# ISL6236A_Sch.net
KiCad netlist of a schematic drawn in Altium Designer
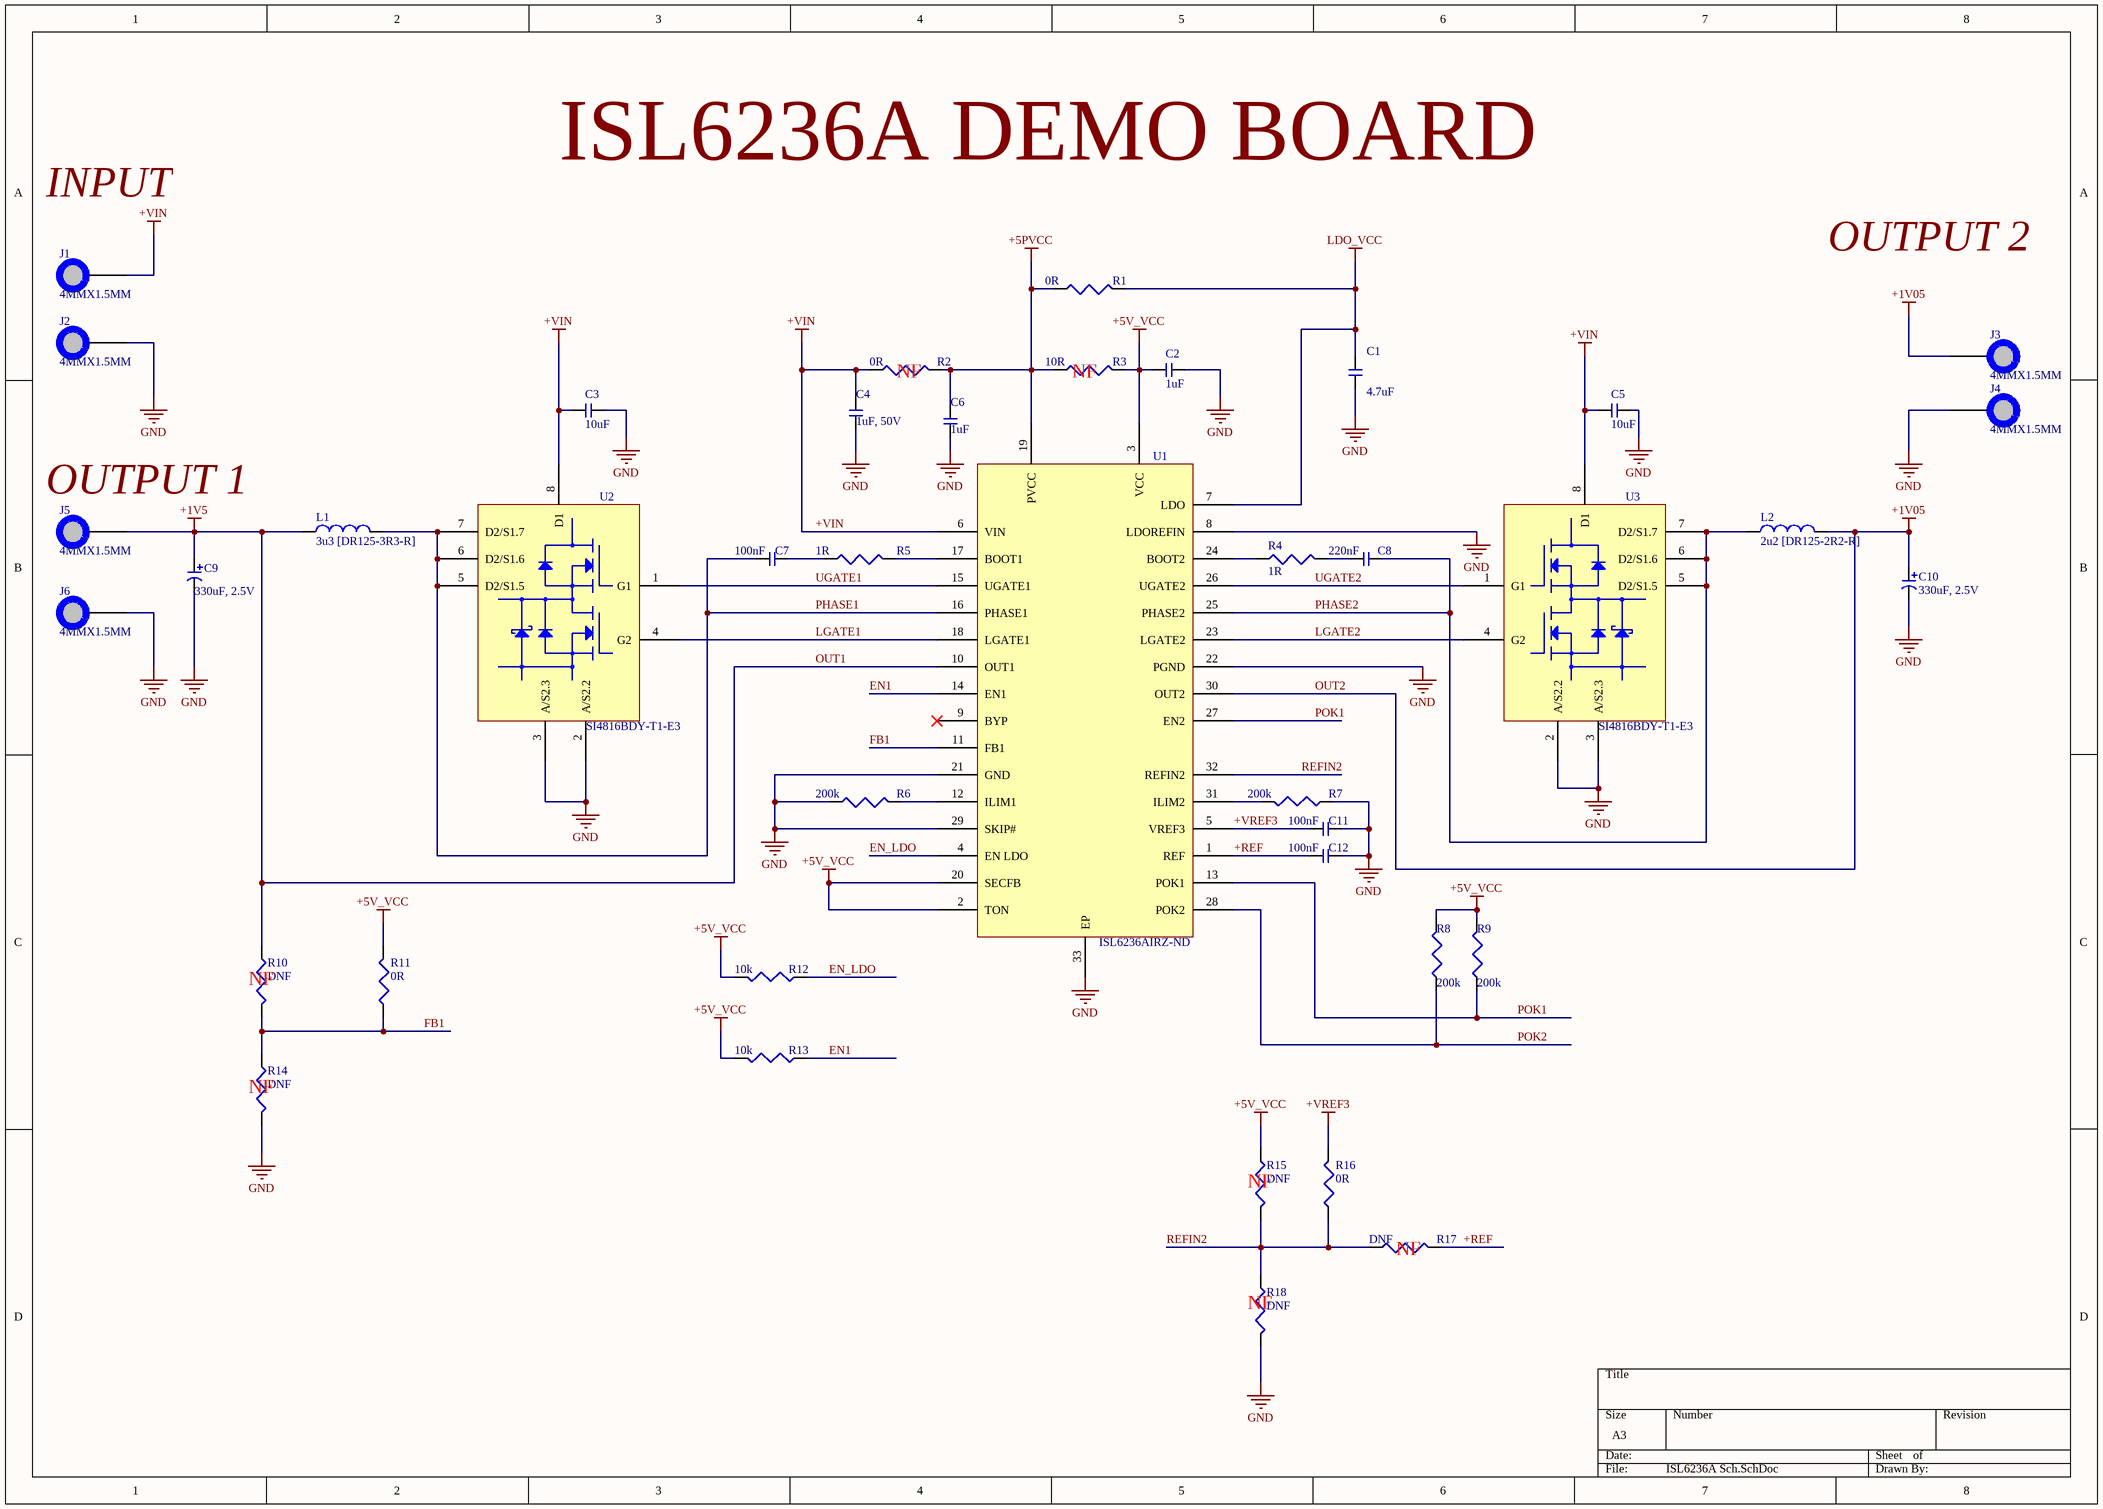
[diagram p0: ISL6236A Sch.SchDoc]

(export (version "E")
  (design (tool "Eeschema 10.0.6"))
  (components
    (comp (ref "C1")
      (value "4.7uF")
      (footprint "C0805")
      (description "CAP CER 4.7UF 10V Y5V 0805")
      (fields
        (field (name "MANUFACTURER") "Yageo")
        (field (name "MANUFACTURER PART NUMBER") "CC0805ZRY5V6BB475")
      )
      (libsource (lib "ISL6236A SchLib") (part "CC0805ZRY5V6BB475"))
    )
    (comp (ref "C2")
      (value "1uF")
      (footprint "C0805")
      (description "CAP CER 1UF 25V X5R 0805")
      (fields
        (field (name "MANUFACTURER") "AVX Corporation")
        (field (name "MANUFACTURER PART NUMBER") "08053D105KAT2A")
      )
      (libsource (lib "ISL6236A SchLib") (part "08053D105KAT2A"))
    )
    (comp (ref "C3")
      (value "10uF")
      (footprint "C1210")
      (description "CAP CER 10UF 25V X5R 1210")
      (fields
        (field (name "MANUFACTURER") "Wurth Electronics Inc")
        (field (name "MANUFACTURER PART NUMBER") "885012109013")
      )
      (libsource (lib "ISL6236A SchLib") (part "885012109013"))
    )
    (comp (ref "C4")
      (value "1uF, 50V")
      (footprint "C0805")
      (description "CAP CER 10000PF 50V NP0 0805")
      (fields
        (field (name "MANUFACTURER") "Murata Electronics North America")
        (field (name "MANUFACTURER PART NUMBER") "GRM2195C1H103FA01D")
      )
      (libsource (lib "ISL6236A SchLib") (part "GRM2195C1H103FA01D"))
    )
    (comp (ref "C5")
      (value "10uF")
      (footprint "C1210")
      (description "CAP CER 10UF 25V X5R 1210")
      (fields
        (field (name "MANUFACTURER") "Wurth Electronics Inc")
        (field (name "MANUFACTURER PART NUMBER") "885012109013")
      )
      (libsource (lib "ISL6236A SchLib") (part "885012109013"))
    )
    (comp (ref "C6")
      (value "1uF")
      (footprint "C0805")
      (description "CAP CER 1UF 25V X5R 0805")
      (fields
        (field (name "MANUFACTURER") "AVX Corporation")
        (field (name "MANUFACTURER PART NUMBER") "08053D105KAT2A")
      )
      (libsource (lib "ISL6236A SchLib") (part "08053D105KAT2A"))
    )
    (comp (ref "C7")
      (value "100nF")
      (footprint "C0805")
      (description "CAP CER 0.1UF 50V X7R 0805")
      (fields
        (field (name "MANUFACTURER") "AVX Corporation")
        (field (name "MANUFACTURER PART NUMBER") "08055C104KAT2A")
      )
      (libsource (lib "ISL6236A SchLib") (part "08055C104KAT2A"))
    )
    (comp (ref "C8")
      (value "220nF")
      (footprint "C1206")
      (description "CAP CER 0.22UF 50V Y5V 1206")
      (fields
        (field (name "MANUFACTURER") "Samsung Electro-Mechanics America, Inc.")
        (field (name "MANUFACTURER PART NUMBER") "CL31F224ZBCNNNC")
      )
      (libsource (lib "ISL6236A SchLib") (part "CL31F224ZBCNNNC"))
    )
    (comp (ref "C9")
      (value "330uF, 2.5V")
      (footprint "CPOL1210TCJ")
      (description "CAP TANT POLY 330UF 2.5V 1210")
      (fields
        (field (name "MANUFACTURER") "AVX Corporation")
        (field (name "MANUFACTURER PART NUMBER") "TCJB337M002R0070")
      )
      (libsource (lib "ISL6236A SchLib") (part "TCJB337M002R0070"))
    )
    (comp (ref "C10")
      (value "330uF, 2.5V")
      (footprint "CPOL1210TCJ")
      (description "CAP TANT POLY 330UF 2.5V 1210")
      (fields
        (field (name "MANUFACTURER") "AVX Corporation")
        (field (name "MANUFACTURER PART NUMBER") "TCJB337M002R0070")
      )
      (libsource (lib "ISL6236A SchLib") (part "TCJB337M002R0070"))
    )
    (comp (ref "C11")
      (value "100nF")
      (footprint "C0805")
      (description "CAP CER 0.1UF 50V X7R 0805")
      (fields
        (field (name "MANUFACTURER") "AVX Corporation")
        (field (name "MANUFACTURER PART NUMBER") "08055C104KAT2A")
      )
      (libsource (lib "ISL6236A SchLib") (part "08055C104KAT2A"))
    )
    (comp (ref "C12")
      (value "100nF")
      (footprint "C0805")
      (description "CAP CER 0.1UF 50V X7R 0805")
      (fields
        (field (name "MANUFACTURER") "AVX Corporation")
        (field (name "MANUFACTURER PART NUMBER") "08055C104KAT2A")
      )
      (libsource (lib "ISL6236A SchLib") (part "08055C104KAT2A"))
    )
    (comp (ref "J1")
      (value "4MMX1.5MM")
      (footprint "PAD_WITH_HOLE_4MMX1.5MM")
      (libsource (lib "ISL6236A SchLib") (part "PAD_WITH_HOLE_4MMX1.5MM"))
    )
    (comp (ref "J2")
      (value "4MMX1.5MM")
      (footprint "PAD_WITH_HOLE_4MMX1.5MM")
      (libsource (lib "ISL6236A SchLib") (part "PAD_WITH_HOLE_4MMX1.5MM"))
    )
    (comp (ref "J3")
      (value "4MMX1.5MM")
      (footprint "PAD_WITH_HOLE_4MMX1.5MM")
      (libsource (lib "ISL6236A SchLib") (part "PAD_WITH_HOLE_4MMX1.5MM"))
    )
    (comp (ref "J4")
      (value "4MMX1.5MM")
      (footprint "PAD_WITH_HOLE_4MMX1.5MM")
      (libsource (lib "ISL6236A SchLib") (part "PAD_WITH_HOLE_4MMX1.5MM"))
    )
    (comp (ref "J5")
      (value "4MMX1.5MM")
      (footprint "PAD_WITH_HOLE_4MMX1.5MM")
      (libsource (lib "ISL6236A SchLib") (part "PAD_WITH_HOLE_4MMX1.5MM"))
    )
    (comp (ref "J6")
      (value "4MMX1.5MM")
      (footprint "PAD_WITH_HOLE_4MMX1.5MM")
      (libsource (lib "ISL6236A SchLib") (part "PAD_WITH_HOLE_4MMX1.5MM"))
    )
    (comp (ref "L1")
      (value "3u3 [DR125-3R3-R]")
      (footprint "DR125")
      (description "FIXED IND 3.3UH 9.26A 6.3 MOHM")
      (fields (field (name "MANUFACTURER") "Eaton") (field (name "MANUFACTURER PART NUMBER") "DR125-3R3-R"))
      (libsource (lib "ISL6236A SchLib") (part "DR125-3R3-R"))
    )
    (comp (ref "L2")
      (value "2u2 [DR125-2R2-R]")
      (footprint "DR125")
      (description "FIXED IND 2.2UH 10.9A 4.5 MOHM")
      (fields (field (name "MANUFACTURER") "Eaton") (field (name "MANUFACTURER PART NUMBER") "DR125-2R2-R"))
      (libsource (lib "ISL6236A SchLib") (part "DR125-2R2-R"))
    )
    (comp (ref "R1")
      (value "0R")
      (footprint "R0603")
      (description "RES SMD 0.0OHM JUMPER 1/10W 0603")
      (fields
        (field (name "MANUFACTURER") "Yageo")
        (field (name "MANUFACTURER PART NUMBER") "RC0603JR-070RL")
      )
      (libsource (lib "ISL6236A SchLib") (part "RC0603JR-070RL"))
    )
    (comp (ref "R2")
      (value "0R")
      (footprint "R0603")
      (description "RES SMD 0.0OHM JUMPER 1/10W 0603")
      (fields
        (field (name "MANUFACTURER") "Yageo")
        (field (name "MANUFACTURER PART NUMBER") "RC0603JR-070RL")
      )
      (libsource (lib "ISL6236A SchLib") (part "RC0603JR-070RL"))
    )
    (comp (ref "R3")
      (value "10R")
      (footprint "R0805")
      (description "RES SMD 10 OHM 5% 0.4W 0805")
      (fields
        (field (name "MANUFACTURER") "Rohm Semiconductor")
        (field (name "MANUFACTURER PART NUMBER") "ESR10EZPJ100")
      )
      (libsource (lib "ISL6236A SchLib") (part "ESR10EZPJ100"))
    )
    (comp (ref "R4")
      (value "1R")
      (footprint "R0805")
      (description "RES SMD 1 OHM 1% 1/8W 0805")
      (fields
        (field (name "MANUFACTURER") "Stackpole Electronics Inc.")
        (field (name "MANUFACTURER PART NUMBER") "RMCF0805FT1R00")
      )
      (libsource (lib "ISL6236A SchLib") (part "RMCF0805FT1R00"))
    )
    (comp (ref "R5")
      (value "1R")
      (footprint "R0805")
      (description "RES SMD 1 OHM 1% 1/8W 0805")
      (fields
        (field (name "MANUFACTURER") "Stackpole Electronics Inc.")
        (field (name "MANUFACTURER PART NUMBER") "RMCF0805FT1R00")
      )
      (libsource (lib "ISL6236A SchLib") (part "RMCF0805FT1R00"))
    )
    (comp (ref "R6")
      (value "200k")
      (footprint "R0805")
      (description "RES SMD 200K OHM 1% 1/8W 0805")
      (fields
        (field (name "MANUFACTURER") "Yageo")
        (field (name "MANUFACTURER PART NUMBER") "RC0805FR-07200KL")
      )
      (libsource (lib "ISL6236A SchLib") (part "RC0805FR-07200KL"))
    )
    (comp (ref "R7")
      (value "200k")
      (footprint "R0805")
      (description "RES SMD 200K OHM 1% 1/8W 0805")
      (fields
        (field (name "MANUFACTURER") "Yageo")
        (field (name "MANUFACTURER PART NUMBER") "RC0805FR-07200KL")
      )
      (libsource (lib "ISL6236A SchLib") (part "RC0805FR-07200KL"))
    )
    (comp (ref "R8")
      (value "200k")
      (footprint "R0805")
      (description "RES SMD 200K OHM 1% 1/8W 0805")
      (fields
        (field (name "MANUFACTURER") "Yageo")
        (field (name "MANUFACTURER PART NUMBER") "RC0805FR-07200KL")
      )
      (libsource (lib "ISL6236A SchLib") (part "RC0805FR-07200KL"))
    )
    (comp (ref "R9")
      (value "200k")
      (footprint "R0805")
      (description "RES SMD 200K OHM 1% 1/8W 0805")
      (fields
        (field (name "MANUFACTURER") "Yageo")
        (field (name "MANUFACTURER PART NUMBER") "RC0805FR-07200KL")
      )
      (libsource (lib "ISL6236A SchLib") (part "RC0805FR-07200KL"))
    )
    (comp (ref "R10") (value "DNF") (footprint "R0805") (libsource (lib "ISL6236A SchLib") (part "RES")))
    (comp (ref "R11")
      (value "0R")
      (footprint "R0603")
      (description "RES SMD 0.0OHM JUMPER 1/10W 0603")
      (fields
        (field (name "MANUFACTURER") "Yageo")
        (field (name "MANUFACTURER PART NUMBER") "RC0603JR-070RL")
      )
      (libsource (lib "ISL6236A SchLib") (part "RC0603JR-070RL"))
    )
    (comp (ref "R12")
      (value "10k")
      (footprint "R0805")
      (description "RES SMD 10K OHM 0.5% 1/10W 0805")
      (fields
        (field (name "MANUFACTURER") "Susumu")
        (field (name "MANUFACTURER PART NUMBER") "RR1220P-103-D")
      )
      (libsource (lib "ISL6236A SchLib") (part "RR1220P-103-D"))
    )
    (comp (ref "R13")
      (value "10k")
      (footprint "R0805")
      (description "RES SMD 10K OHM 0.5% 1/10W 0805")
      (fields
        (field (name "MANUFACTURER") "Susumu")
        (field (name "MANUFACTURER PART NUMBER") "RR1220P-103-D")
      )
      (libsource (lib "ISL6236A SchLib") (part "RR1220P-103-D"))
    )
    (comp (ref "R14") (value "DNF") (footprint "R0805") (libsource (lib "ISL6236A SchLib") (part "RES")))
    (comp (ref "R15") (value "DNF") (footprint "R0805") (libsource (lib "ISL6236A SchLib") (part "RES")))
    (comp (ref "R16")
      (value "0R")
      (footprint "R0603")
      (description "RES SMD 0.0OHM JUMPER 1/10W 0603")
      (fields
        (field (name "MANUFACTURER") "Yageo")
        (field (name "MANUFACTURER PART NUMBER") "RC0603JR-070RL")
      )
      (libsource (lib "ISL6236A SchLib") (part "RC0603JR-070RL"))
    )
    (comp (ref "R17") (value "DNF") (footprint "R0805") (libsource (lib "ISL6236A SchLib") (part "RES")))
    (comp (ref "R18") (value "DNF") (footprint "R0805") (libsource (lib "ISL6236A SchLib") (part "RES")))
    (comp (ref "U1")
      (value "ISL6236AIRZ-ND")
      (footprint "L32.5x5B")
      (description "IC MAIN PWR CTRLR QUAD 32-QFN")
      (fields
        (field (name "MANUFACTURER") "Intersil")
        (field (name "MANUFACTURER PART NUMBER") "ISL6236AIRZ")
      )
      (libsource (lib "ISL6236A SchLib") (part "ISL6236AIRZ"))
    )
    (comp (ref "U2")
      (value "SI4816BDY-T1-E3")
      (footprint "SO-8")
      (description "MOSFET 2N-CH 30V 5.8A 8-SOIC")
      (fields (field (name "MANUFACTURER") "Vishay Siliconix"))
      (libsource (lib "ISL6236A SchLib") (part "SI4816BDY-T1-E3"))
    )
    (comp (ref "U3")
      (value "SI4816BDY-T1-E3")
      (footprint "SO-8")
      (description "MOSFET 2N-CH 30V 5.8A 8-SOIC")
      (fields (field (name "MANUFACTURER") "Vishay Siliconix"))
      (libsource (lib "ISL6236A SchLib") (part "SI4816BDY-T1-E3"))
    )
  )
  (nets
    (net (code "1") (name "+1V05") (class "Default")
      (node (ref "C10") (pin "1") (pinfunction "1_1") (pintype "passive"))
      (node (ref "J3") (pin "1") (pinfunction "1_1") (pintype "passive"))
      (node (ref "L2") (pin "2") (pinfunction "2_2") (pintype "power_in"))
      (node (ref "U1") (pin "30") (pinfunction "OUT2_30") (pintype "power_in"))
    )
    (net (code "2") (name "+1V5") (class "Default")
      (node (ref "C9") (pin "1") (pinfunction "1_1") (pintype "passive"))
      (node (ref "J5") (pin "1") (pinfunction "1_1") (pintype "passive"))
      (node (ref "L1") (pin "1") (pinfunction "1_1") (pintype "power_in"))
      (node (ref "R10") (pin "1") (pinfunction "1_1") (pintype "passive"))
      (node (ref "U1") (pin "10") (pinfunction "OUT1_10") (pintype "power_in"))
    )
    (net (code "3") (name "+5PVCC") (class "Default")
      (node (ref "C6") (pin "2") (pinfunction "2_2") (pintype "passive"))
      (node (ref "R1") (pin "1") (pinfunction "1_1") (pintype "power_in"))
      (node (ref "R2") (pin "2") (pinfunction "2_2") (pintype "power_in"))
      (node (ref "R3") (pin "1") (pinfunction "1_1") (pintype "power_in"))
      (node (ref "U1") (pin "19") (pinfunction "PVCC_19") (pintype "power_in"))
    )
    (net (code "4") (name "+5V_VCC") (class "Default")
      (node (ref "C2") (pin "1") (pinfunction "1_1") (pintype "passive"))
      (node (ref "R11") (pin "2") (pinfunction "2_2") (pintype "power_in"))
      (node (ref "R12") (pin "2") (pinfunction "2_2") (pintype "power_in"))
      (node (ref "R13") (pin "2") (pinfunction "2_2") (pintype "power_in"))
      (node (ref "R15") (pin "1") (pinfunction "1_1") (pintype "passive"))
      (node (ref "R3") (pin "2") (pinfunction "2_2") (pintype "power_in"))
      (node (ref "R8") (pin "2") (pinfunction "2_2") (pintype "power_in"))
      (node (ref "R9") (pin "2") (pinfunction "2_2") (pintype "power_in"))
      (node (ref "U1") (pin "2") (pinfunction "TON_2") (pintype "power_in"))
      (node (ref "U1") (pin "20") (pinfunction "SECFB_20") (pintype "power_in"))
      (node (ref "U1") (pin "3") (pinfunction "VCC_3") (pintype "power_in"))
    )
    (net (code "5") (name "+VIN") (class "Default")
      (node (ref "C3") (pin "2") (pinfunction "2_2") (pintype "passive"))
      (node (ref "C4") (pin "1") (pinfunction "1_1") (pintype "passive"))
      (node (ref "C5") (pin "1") (pinfunction "1_1") (pintype "passive"))
      (node (ref "J1") (pin "1") (pinfunction "1_1") (pintype "passive"))
      (node (ref "R2") (pin "1") (pinfunction "1_1") (pintype "power_in"))
      (node (ref "U1") (pin "6") (pinfunction "VIN_6") (pintype "power_in"))
      (node (ref "U2") (pin "8") (pinfunction "D1_8") (pintype "power_in"))
      (node (ref "U3") (pin "8") (pinfunction "D1_8") (pintype "power_in"))
    )
    (net (code "6") (name "+VREF3") (class "Default")
      (node (ref "C11") (pin "1") (pinfunction "1_1") (pintype "passive"))
      (node (ref "R16") (pin "2") (pinfunction "2_2") (pintype "power_in"))
      (node (ref "U1") (pin "5") (pinfunction "VREF3_5") (pintype "power_in"))
    )
    (net (code "7") (name "/+REF") (class "Default")
      (node (ref "C12") (pin "1") (pinfunction "1_1") (pintype "passive"))
      (node (ref "R17") (pin "2") (pinfunction "2_2") (pintype "passive"))
      (node (ref "U1") (pin "1") (pinfunction "REF_1") (pintype "power_in"))
    )
    (net (code "8") (name "/EN1") (class "Default")
      (node (ref "R13") (pin "1") (pinfunction "1_1") (pintype "power_in"))
      (node (ref "U1") (pin "14") (pinfunction "EN1_14") (pintype "power_in"))
    )
    (net (code "9") (name "/EN_LDO") (class "Default")
      (node (ref "R12") (pin "1") (pinfunction "1_1") (pintype "power_in"))
      (node (ref "U1") (pin "4") (pinfunction "EN_LDO_4") (pintype "power_in"))
    )
    (net (code "10") (name "/FB1") (class "Default")
      (node (ref "R10") (pin "2") (pinfunction "2_2") (pintype "passive"))
      (node (ref "R11") (pin "1") (pinfunction "1_1") (pintype "power_in"))
      (node (ref "R14") (pin "1") (pinfunction "1_1") (pintype "passive"))
      (node (ref "U1") (pin "11") (pinfunction "FB1_11") (pintype "power_in"))
    )
    (net (code "11") (name "/LGATE1") (class "Default")
      (node (ref "U1") (pin "18") (pinfunction "LGATE1_18") (pintype "power_in"))
      (node (ref "U2") (pin "4") (pinfunction "G2_4") (pintype "power_in"))
    )
    (net (code "12") (name "/LGATE2") (class "Default")
      (node (ref "U1") (pin "23") (pinfunction "LGATE2_23") (pintype "power_in"))
      (node (ref "U3") (pin "4") (pinfunction "G2_4") (pintype "power_in"))
    )
    (net (code "13") (name "/PHASE1") (class "Default")
      (node (ref "C7") (pin "2") (pinfunction "2_2") (pintype "passive"))
      (node (ref "L1") (pin "2") (pinfunction "2_2") (pintype "power_in"))
      (node (ref "U1") (pin "16") (pinfunction "PHASE1_16") (pintype "power_in"))
      (node (ref "U2") (pin "5") (pinfunction "D2/S1.5_5") (pintype "power_in"))
      (node (ref "U2") (pin "6") (pinfunction "D2/S1.6_6") (pintype "power_in"))
      (node (ref "U2") (pin "7") (pinfunction "D2/S1.7_7") (pintype "power_in"))
    )
    (net (code "14") (name "/PHASE2") (class "Default")
      (node (ref "C8") (pin "2") (pinfunction "2_2") (pintype "passive"))
      (node (ref "L2") (pin "1") (pinfunction "1_1") (pintype "power_in"))
      (node (ref "U1") (pin "25") (pinfunction "PHASE2_25") (pintype "power_in"))
      (node (ref "U3") (pin "5") (pinfunction "D2/S1.5_5") (pintype "power_in"))
      (node (ref "U3") (pin "6") (pinfunction "D2/S1.6_6") (pintype "power_in"))
      (node (ref "U3") (pin "7") (pinfunction "D2/S1.7_7") (pintype "power_in"))
    )
    (net (code "15") (name "/POK1") (class "Default")
      (node (ref "R9") (pin "1") (pinfunction "1_1") (pintype "power_in"))
      (node (ref "U1") (pin "13") (pinfunction "POK1_13") (pintype "power_in"))
      (node (ref "U1") (pin "27") (pinfunction "EN2_27") (pintype "power_in"))
    )
    (net (code "16") (name "/POK2") (class "Default")
      (node (ref "R8") (pin "1") (pinfunction "1_1") (pintype "power_in"))
      (node (ref "U1") (pin "28") (pinfunction "POK2_28") (pintype "power_in"))
    )
    (net (code "17") (name "/REFIN2") (class "Default")
      (node (ref "R15") (pin "2") (pinfunction "2_2") (pintype "passive"))
      (node (ref "R16") (pin "1") (pinfunction "1_1") (pintype "power_in"))
      (node (ref "R17") (pin "1") (pinfunction "1_1") (pintype "passive"))
      (node (ref "R18") (pin "1") (pinfunction "1_1") (pintype "passive"))
      (node (ref "U1") (pin "32") (pinfunction "REFIN2_32") (pintype "power_in"))
    )
    (net (code "18") (name "/UGATE1") (class "Default")
      (node (ref "U1") (pin "15") (pinfunction "UGATE1_15") (pintype "power_in"))
      (node (ref "U2") (pin "1") (pinfunction "G1_1") (pintype "power_in"))
    )
    (net (code "19") (name "/UGATE2") (class "Default")
      (node (ref "U1") (pin "26") (pinfunction "UGATE2_26") (pintype "passive"))
      (node (ref "U3") (pin "1") (pinfunction "G1_1") (pintype "power_in"))
    )
    (net (code "20") (name "GND") (class "Default")
      (node (ref "C1") (pin "2") (pinfunction "2_2") (pintype "passive"))
      (node (ref "C10") (pin "2") (pinfunction "2_2") (pintype "passive"))
      (node (ref "C11") (pin "2") (pinfunction "2_2") (pintype "passive"))
      (node (ref "C12") (pin "2") (pinfunction "2_2") (pintype "passive"))
      (node (ref "C2") (pin "2") (pinfunction "2_2") (pintype "passive"))
      (node (ref "C3") (pin "1") (pinfunction "1_1") (pintype "passive"))
      (node (ref "C4") (pin "2") (pinfunction "2_2") (pintype "passive"))
      (node (ref "C5") (pin "2") (pinfunction "2_2") (pintype "passive"))
      (node (ref "C6") (pin "1") (pinfunction "1_1") (pintype "passive"))
      (node (ref "C9") (pin "2") (pinfunction "2_2") (pintype "passive"))
      (node (ref "J2") (pin "1") (pinfunction "1_1") (pintype "passive"))
      (node (ref "J4") (pin "1") (pinfunction "1_1") (pintype "passive"))
      (node (ref "J6") (pin "1") (pinfunction "1_1") (pintype "passive"))
      (node (ref "R14") (pin "2") (pinfunction "2_2") (pintype "passive"))
      (node (ref "R18") (pin "2") (pinfunction "2_2") (pintype "passive"))
      (node (ref "R6") (pin "1") (pinfunction "1_1") (pintype "power_in"))
      (node (ref "R7") (pin "1") (pinfunction "1_1") (pintype "power_in"))
      (node (ref "U1") (pin "21") (pinfunction "GND_21") (pintype "power_in"))
      (node (ref "U1") (pin "22") (pinfunction "PGND_22") (pintype "power_in"))
      (node (ref "U1") (pin "29") (pinfunction "SKIP#_29") (pintype "power_in"))
      (node (ref "U1") (pin "33") (pinfunction "EP_33") (pintype "power_in"))
      (node (ref "U1") (pin "8") (pinfunction "LDOREFIN_8") (pintype "power_in"))
      (node (ref "U2") (pin "2") (pinfunction "A/S2.2_2") (pintype "power_in"))
      (node (ref "U2") (pin "3") (pinfunction "A/S2.3_3") (pintype "power_in"))
      (node (ref "U3") (pin "2") (pinfunction "A/S2.2_2") (pintype "power_in"))
      (node (ref "U3") (pin "3") (pinfunction "A/S2.3_3") (pintype "power_in"))
    )
    (net (code "21") (name "LDO_VCC") (class "Default")
      (node (ref "C1") (pin "1") (pinfunction "1_1") (pintype "passive"))
      (node (ref "R1") (pin "2") (pinfunction "2_2") (pintype "power_in"))
      (node (ref "U1") (pin "7") (pinfunction "LDO_7") (pintype "power_in"))
    )
    (net (code "22") (name "Net-(C7-Pad1)") (class "Default")
      (node (ref "C7") (pin "1") (pinfunction "1_1") (pintype "passive"))
      (node (ref "R5") (pin "1") (pinfunction "1_1") (pintype "power_in"))
    )
    (net (code "23") (name "Net-(C8-Pad1)") (class "Default")
      (node (ref "C8") (pin "1") (pinfunction "1_1") (pintype "passive"))
      (node (ref "R4") (pin "2") (pinfunction "2_2") (pintype "power_in"))
    )
    (net (code "24") (name "Net-(U1-BOOT1)") (class "Default")
      (node (ref "R5") (pin "2") (pinfunction "2_2") (pintype "power_in"))
      (node (ref "U1") (pin "17") (pinfunction "BOOT1_17") (pintype "power_in"))
    )
    (net (code "25") (name "Net-(U1-BOOT2)") (class "Default")
      (node (ref "R4") (pin "1") (pinfunction "1_1") (pintype "power_in"))
      (node (ref "U1") (pin "24") (pinfunction "BOOT2_24") (pintype "power_in"))
    )
    (net (code "26") (name "Net-(U1-ILIM1)") (class "Default")
      (node (ref "R6") (pin "2") (pinfunction "2_2") (pintype "power_in"))
      (node (ref "U1") (pin "12") (pinfunction "ILIM1_12") (pintype "power_in"))
    )
    (net (code "27") (name "Net-(U1-ILIM2)") (class "Default")
      (node (ref "R7") (pin "2") (pinfunction "2_2") (pintype "power_in"))
      (node (ref "U1") (pin "31") (pinfunction "ILIM2_31") (pintype "power_in"))
    )
    (net (code "28") (name "unconnected-(U1-BYP-Pad9)") (class "Default")
      (node (ref "U1") (pin "9") (pinfunction "BYP_9") (pintype "power_in+no_connect"))
    )
  )
)
